# Sheet5.net
KiCad netlist of a schematic drawn in Altium Designer
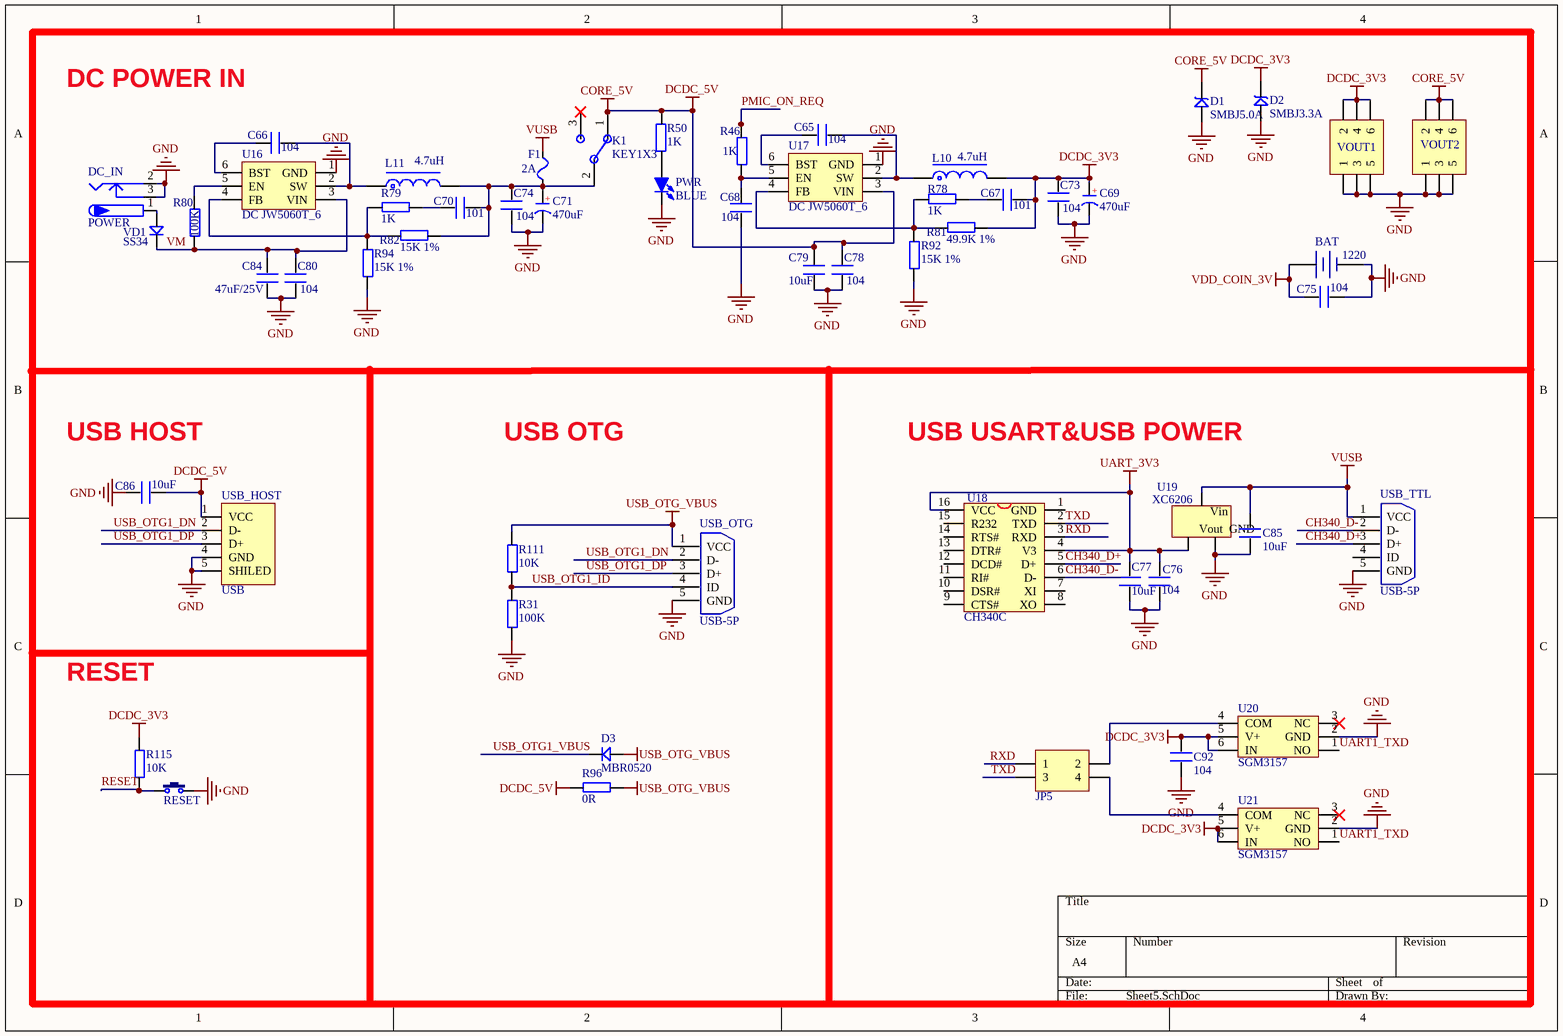
[diagram p0: Sheet5.SchDoc]

(export (version "E")
  (design (tool "Eeschema 10.0.6"))
  (components
    (comp (ref "BAT")
      (value "1220")
      (footprint "CR1220_B")
      (description "微型电池")
      (fields (field (name "版权归属") "源创客"))
      (libsource (lib "linux_board_SCH") (part "CR-3V"))
    )
    (comp (ref "C65") (value "104") (footprint "C 0603") (libsource (lib "linux_board_SCH") (part "C")))
    (comp (ref "C66") (value "104") (footprint "C 0603") (libsource (lib "linux_board_SCH") (part "C")))
    (comp (ref "C67") (value "101") (footprint "C 0603") (libsource (lib "linux_board_SCH") (part "C")))
    (comp (ref "C68") (value "104") (footprint "C 0603") (libsource (lib "linux_board_SCH") (part "C")))
    (comp (ref "C69")
      (value "470uF")
      (footprint "CM D(6.3*5.4)")
      (description "贴片电解电容")
      (fields (field (name "版权归属") "源创客"))
      (libsource (lib "linux_board_SCH") (part "C-CM"))
    )
    (comp (ref "C70") (value "101") (footprint "C 0603") (libsource (lib "linux_board_SCH") (part "C")))
    (comp (ref "C71")
      (value "470uF")
      (footprint "CM D(6.3*5.4)")
      (description "贴片电解电容")
      (fields (field (name "版权归属") "源创客"))
      (libsource (lib "linux_board_SCH") (part "C-CM"))
    )
    (comp (ref "C73") (value "104") (footprint "C 0603") (libsource (lib "linux_board_SCH") (part "C")))
    (comp (ref "C74") (value "104") (footprint "C 0603") (libsource (lib "linux_board_SCH") (part "C")))
    (comp (ref "C75") (value "104") (footprint "C 0603") (libsource (lib "linux_board_SCH") (part "C")))
    (comp (ref "C76") (value "104") (footprint "C 0603") (libsource (lib "linux_board_SCH") (part "C")))
    (comp (ref "C77") (value "10uF") (footprint "C 0603") (libsource (lib "linux_board_SCH") (part "C")))
    (comp (ref "C78") (value "104") (footprint "C 0603") (libsource (lib "linux_board_SCH") (part "C")))
    (comp (ref "C79") (value "10uF") (footprint "C 0603") (libsource (lib "linux_board_SCH") (part "C")))
    (comp (ref "C80") (value "104") (footprint "C 0603") (libsource (lib "linux_board_SCH") (part "C")))
    (comp (ref "C84") (value "47uF/25V") (footprint "C 0603") (libsource (lib "linux_board_SCH") (part "C")))
    (comp (ref "C85") (value "10uF") (footprint "C 0603") (libsource (lib "linux_board_SCH") (part "C")))
    (comp (ref "C86") (value "10uF") (footprint "C 0603") (libsource (lib "linux_board_SCH") (part "C")))
    (comp (ref "C92") (value "104") (footprint "C 0603") (libsource (lib "linux_board_SCH") (part "C")))
    (comp (ref "D1")
      (value "SMBJ5.0A")
      (footprint "SMBJ")
      (description "TVS")
      (libsource (lib "linux_board_SCH") (part "SMBJ"))
    )
    (comp (ref "D2")
      (value "SMBJ3.3A")
      (footprint "SMBJ")
      (description "TVS")
      (libsource (lib "linux_board_SCH") (part "SMBJ"))
    )
    (comp (ref "D3")
      (value "MBR0520")
      (footprint "SOD-123F")
      (description "肖特基二极管")
      (fields (field (name "版权归属") "源创客"))
      (libsource (lib "linux_board_SCH") (part "SS14"))
    )
    (comp (ref "DC_IN")
      (value "POWER")
      (footprint "DC10B")
      (description "低压电源接口")
      (fields (field (name "版权归属") "源创客"))
      (libsource (lib "linux_board_SCH") (part "P-DC"))
    )
    (comp (ref "F1")
      (value "2A")
      (footprint "FU 1206")
      (description "贴片保险丝")
      (fields (field (name "版权归属") "源创客"))
      (libsource (lib "linux_board_SCH") (part "FU"))
    )
    (comp (ref "JP5")
      (value "Header2X2")
      (footprint "HDR-2X2")
      (description "2*2P接插件")
      (fields (field (name "版权归属") "源创客"))
      (libsource (lib "linux_board_SCH") (part "Header 2X2"))
    )
    (comp (ref "K1") (value "KEY1X3") (footprint "PKEY") (libsource (lib "linux_board_SCH") (part "PKEY")))
    (comp (ref "L10")
      (value "4.7uH")
      (footprint "L-SMD-0420")
      (description "功率屏蔽电感")
      (fields (field (name "版权归属") "源创客"))
      (libsource (lib "linux_board_SCH") (part "L-CDRH"))
    )
    (comp (ref "L11")
      (value "4.7uH")
      (footprint "L-SMD-0420")
      (description "功率屏蔽电感")
      (fields (field (name "版权归属") "源创客"))
      (libsource (lib "linux_board_SCH") (part "L-CDRH"))
    )
    (comp (ref "PWR")
      (value "BLUE")
      (footprint "LED 0805R")
      (description "贴片LED")
      (fields (field (name "版权归属") "源创客"))
      (libsource (lib "linux_board_SCH") (part "LED-SMD"))
    )
    (comp (ref "R31") (value "100K") (footprint "R 0603") (libsource (lib "linux_board_SCH") (part "R")))
    (comp (ref "R46") (value "1K") (footprint "R 0603") (libsource (lib "linux_board_SCH") (part "R")))
    (comp (ref "R50") (value "1K") (footprint "R 0603") (libsource (lib "linux_board_SCH") (part "R")))
    (comp (ref "R78") (value "1K") (footprint "R 0603") (libsource (lib "linux_board_SCH") (part "R")))
    (comp (ref "R79") (value "1K") (footprint "R 0603") (libsource (lib "linux_board_SCH") (part "R")))
    (comp (ref "R80") (value "100K") (footprint "R 0603") (libsource (lib "linux_board_SCH") (part "R")))
    (comp (ref "R81") (value "49.9K 1%") (footprint "R 0603") (libsource (lib "linux_board_SCH") (part "R")))
    (comp (ref "R82") (value "15K 1%") (footprint "R 0603") (libsource (lib "linux_board_SCH") (part "R")))
    (comp (ref "R92") (value "15K 1%") (footprint "R 0603") (libsource (lib "linux_board_SCH") (part "R")))
    (comp (ref "R94") (value "15K 1%") (footprint "R 0603") (libsource (lib "linux_board_SCH") (part "R")))
    (comp (ref "R96") (value "0R") (footprint "R 0603") (libsource (lib "linux_board_SCH") (part "R")))
    (comp (ref "R111") (value "10K") (footprint "R 0603") (libsource (lib "linux_board_SCH") (part "R")))
    (comp (ref "R115") (value "10K") (footprint "R 0603") (libsource (lib "linux_board_SCH") (part "R")))
    (comp (ref "RESET")
      (value "KEY")
      (footprint "TSW DIP-6*6*5 - 2")
      (description "按键")
      (fields (field (name "版权归属") "源创客"))
      (libsource (lib "linux_board_SCH") (part "KEY"))
    )
    (comp (ref "U16")
      (value "DC JW5060T_6")
      (footprint "SOT23-6N")
      (description "DC降压芯片")
      (libsource (lib "linux_board_SCH") (part "DC JW5060T_6"))
    )
    (comp (ref "U17")
      (value "DC JW5060T_6")
      (footprint "SOT23-6N")
      (description "DC降压芯片")
      (libsource (lib "linux_board_SCH") (part "DC JW5060T_6"))
    )
    (comp (ref "U18")
      (value "CH340C")
      (footprint "SOP16_N")
      (description "USB2UART")
      (libsource (lib "linux_board_SCH") (part "CH340G"))
    )
    (comp (ref "U19")
      (value "XC6206")
      (footprint "SOT23-3N")
      (description "LDO")
      (libsource (lib "linux_board_SCH") (part "LDO XC6206"))
    )
    (comp (ref "U20")
      (value "SGM3157")
      (footprint "SOT363-6L")
      (description "单路双掷模拟开关")
      (libsource (lib "linux_board_SCH") (part "SGM3157"))
    )
    (comp (ref "U21")
      (value "SGM3157")
      (footprint "SOT363-6L")
      (description "单路双掷模拟开关")
      (libsource (lib "linux_board_SCH") (part "SGM3157"))
    )
    (comp (ref "USB_HOST")
      (value "USB")
      (footprint "USB-A/S_E")
      (description "USB-A型母接口")
      (fields (field (name "版权归属") "源创客"))
      (libsource (lib "linux_board_SCH") (part "USB-A/S"))
    )
    (comp (ref "USB_OTG")
      (value "USB-5P")
      (footprint "USB-MINI-A")
      (description "微型USB母座")
      (fields (field (name "版权归属") "源创客"))
      (libsource (lib "linux_board_SCH") (part "USB-5P"))
    )
    (comp (ref "USB_TTL")
      (value "USB-5P")
      (footprint "USB-MINI-A")
      (description "微型USB母座")
      (fields (field (name "版权归属") "源创客"))
      (libsource (lib "linux_board_SCH") (part "USB-5P"))
    )
    (comp (ref "VD1")
      (value "SS34")
      (footprint "SOD-323")
      (description "肖特基二极管")
      (fields (field (name "版权归属") "源创客"))
      (libsource (lib "linux_board_SCH") (part "SS14"))
    )
    (comp (ref "VOUT1")
      (value "RS232/RS485")
      (footprint "HDR-3X2")
      (description "3*2P接插件")
      (fields (field (name "版权归属") "源创客"))
      (libsource (lib "linux_board_SCH") (part "Header 3X2"))
    )
    (comp (ref "VOUT2")
      (value "RS232/RS485")
      (footprint "HDR-3X2")
      (description "3*2P接插件")
      (fields (field (name "版权归属") "源创客"))
      (libsource (lib "linux_board_SCH") (part "Header 3X2"))
    )
  )
  (nets
    (net (code "1") (name "/CH340_D+") (class "Default")
      (node (ref "U18") (pin "5") (pinfunction "D+_5") (pintype "passive"))
      (node (ref "USB_TTL") (pin "3") (pinfunction "D+_3") (pintype "passive"))
    )
    (net (code "2") (name "/CH340_D-") (class "Default")
      (node (ref "U18") (pin "6") (pinfunction "D-_6") (pintype "passive"))
      (node (ref "USB_TTL") (pin "2") (pinfunction "D-_2") (pintype "passive"))
    )
    (net (code "3") (name "/PMIC_ON_REQ") (class "Default") (node (ref "R46") (pin "2") (pintype "passive")))
    (net (code "4") (name "/RESET") (class "Default")
      (node (ref "R115") (pin "1") (pintype "passive"))
      (node (ref "RESET") (pin "1") (pinfunction "1_1") (pintype "passive"))
    )
    (net (code "5") (name "/RXD") (class "Default")
      (node (ref "JP5") (pin "1") (pinfunction "1_1") (pintype "passive"))
      (node (ref "U18") (pin "3") (pinfunction "RXD_3") (pintype "passive"))
    )
    (net (code "6") (name "/TXD") (class "Default")
      (node (ref "JP5") (pin "3") (pinfunction "3_3") (pintype "passive"))
      (node (ref "U18") (pin "2") (pinfunction "TXD_2") (pintype "passive"))
    )
    (net (code "7") (name "/UART1_TXD") (class "Default")
      (node (ref "U20") (pin "1") (pinfunction "NO_1") (pintype "passive"))
      (node (ref "U21") (pin "1") (pinfunction "NO_1") (pintype "passive"))
    )
    (net (code "8") (name "/USB_OTG1_DN") (class "Default")
      (node (ref "USB_HOST") (pin "2") (pinfunction "D-_2") (pintype "passive"))
      (node (ref "USB_OTG") (pin "2") (pinfunction "D-_2") (pintype "passive"))
    )
    (net (code "9") (name "/USB_OTG1_DP") (class "Default")
      (node (ref "USB_HOST") (pin "3") (pinfunction "D+_3") (pintype "passive"))
      (node (ref "USB_OTG") (pin "3") (pinfunction "D+_3") (pintype "passive"))
    )
    (net (code "10") (name "/USB_OTG1_ID") (class "Default")
      (node (ref "R111") (pin "1") (pintype "passive"))
      (node (ref "R31") (pin "2") (pintype "passive"))
      (node (ref "USB_OTG") (pin "4") (pinfunction "ID_4") (pintype "passive"))
    )
    (net (code "11") (name "/USB_OTG1_VBUS") (class "Default")
      (node (ref "D3") (pin "2") (pinfunction "K_2") (pintype "passive"))
    )
    (net (code "12") (name "/VM") (class "Default")
      (node (ref "C80") (pin "2") (pintype "passive"))
      (node (ref "C84") (pin "2") (pintype "passive"))
      (node (ref "R80") (pin "1") (pintype "passive"))
      (node (ref "U16") (pin "3") (pinfunction "VIN_3") (pintype "passive"))
      (node (ref "VD1") (pin "2") (pinfunction "K_2") (pintype "passive"))
    )
    (net (code "13") (name "CORE_5V") (class "Default")
      (node (ref "C78") (pin "2") (pintype "passive"))
      (node (ref "C79") (pin "2") (pintype "passive"))
      (node (ref "C86") (pin "1") (pintype "passive"))
      (node (ref "D1") (pin "2") (pintype "passive"))
      (node (ref "K1") (pin "1") (pintype "passive"))
      (node (ref "R50") (pin "1") (pintype "passive"))
      (node (ref "R96") (pin "2") (pintype "passive"))
      (node (ref "U17") (pin "3") (pinfunction "VIN_3") (pintype "passive"))
      (node (ref "USB_HOST") (pin "1") (pinfunction "VCC_1") (pintype "passive"))
      (node (ref "VOUT2") (pin "2") (pinfunction "2_2") (pintype "passive"))
      (node (ref "VOUT2") (pin "4") (pinfunction "4_4") (pintype "passive"))
      (node (ref "VOUT2") (pin "6") (pinfunction "6_6") (pintype "passive"))
    )
    (net (code "14") (name "DCDC_3V3") (class "Default")
      (node (ref "C67") (pin "2") (pintype "passive"))
      (node (ref "C69") (pin "1") (pinfunction "A_1") (pintype "passive"))
      (node (ref "C73") (pin "2") (pintype "passive"))
      (node (ref "C92") (pin "2") (pintype "passive"))
      (node (ref "D2") (pin "2") (pintype "passive"))
      (node (ref "L10") (pin "2") (pinfunction "2_2") (pintype "passive"))
      (node (ref "R115") (pin "2") (pintype "passive"))
      (node (ref "R81") (pin "1") (pintype "passive"))
      (node (ref "U20") (pin "5") (pinfunction "V+_5") (pintype "passive"))
      (node (ref "U20") (pin "6") (pinfunction "IN_6") (pintype "passive"))
      (node (ref "U21") (pin "5") (pinfunction "V+_5") (pintype "passive"))
      (node (ref "U21") (pin "6") (pinfunction "IN_6") (pintype "passive"))
      (node (ref "VOUT1") (pin "2") (pinfunction "2_2") (pintype "passive"))
      (node (ref "VOUT1") (pin "4") (pinfunction "4_4") (pintype "passive"))
      (node (ref "VOUT1") (pin "6") (pinfunction "6_6") (pintype "passive"))
    )
    (net (code "15") (name "GND") (class "Default")
      (node (ref "BAT") (pin "2") (pinfunction "DC-_2") (pintype "passive"))
      (node (ref "C68") (pin "1") (pintype "passive"))
      (node (ref "C69") (pin "2") (pinfunction "K_2") (pintype "passive"))
      (node (ref "C71") (pin "2") (pinfunction "K_2") (pintype "passive"))
      (node (ref "C73") (pin "1") (pintype "passive"))
      (node (ref "C74") (pin "1") (pintype "passive"))
      (node (ref "C75") (pin "2") (pintype "passive"))
      (node (ref "C76") (pin "1") (pintype "passive"))
      (node (ref "C77") (pin "1") (pintype "passive"))
      (node (ref "C78") (pin "1") (pintype "passive"))
      (node (ref "C79") (pin "1") (pintype "passive"))
      (node (ref "C80") (pin "1") (pintype "passive"))
      (node (ref "C84") (pin "1") (pintype "passive"))
      (node (ref "C85") (pin "1") (pintype "passive"))
      (node (ref "C86") (pin "2") (pintype "passive"))
      (node (ref "C92") (pin "1") (pintype "passive"))
      (node (ref "D1") (pin "1") (pintype "passive"))
      (node (ref "D2") (pin "1") (pintype "passive"))
      (node (ref "DC_IN") (pin "2") (pintype "power_in"))
      (node (ref "DC_IN") (pin "3") (pintype "power_in"))
      (node (ref "PWR") (pin "2") (pinfunction "K_2") (pintype "passive"))
      (node (ref "R31") (pin "1") (pintype "passive"))
      (node (ref "R92") (pin "1") (pintype "passive"))
      (node (ref "R94") (pin "1") (pintype "passive"))
      (node (ref "RESET") (pin "2") (pinfunction "2_2") (pintype "passive"))
      (node (ref "U16") (pin "1") (pinfunction "GND_1") (pintype "passive"))
      (node (ref "U17") (pin "1") (pinfunction "GND_1") (pintype "passive"))
      (node (ref "U19") (pin "1") (pinfunction "GND_1") (pintype "passive"))
      (node (ref "U20") (pin "2") (pinfunction "GND_2") (pintype "passive"))
      (node (ref "U21") (pin "2") (pinfunction "GND_2") (pintype "passive"))
      (node (ref "USB_HOST") (pin "4") (pinfunction "GND_4") (pintype "passive"))
      (node (ref "USB_HOST") (pin "5") (pinfunction "SHILED_5") (pintype "passive"))
      (node (ref "USB_OTG") (pin "5") (pinfunction "GND_5") (pintype "passive"))
      (node (ref "USB_TTL") (pin "5") (pinfunction "GND_5") (pintype "passive"))
      (node (ref "VOUT1") (pin "1") (pinfunction "1_1") (pintype "passive"))
      (node (ref "VOUT1") (pin "3") (pinfunction "3_3") (pintype "passive"))
      (node (ref "VOUT1") (pin "5") (pinfunction "5_5") (pintype "passive"))
      (node (ref "VOUT2") (pin "1") (pinfunction "1_1") (pintype "passive"))
      (node (ref "VOUT2") (pin "3") (pinfunction "3_3") (pintype "passive"))
      (node (ref "VOUT2") (pin "5") (pinfunction "5_5") (pintype "passive"))
    )
    (net (code "16") (name "Net-(C67-Pad1)") (class "Default")
      (node (ref "C67") (pin "1") (pintype "passive"))
      (node (ref "R78") (pin "1") (pintype "passive"))
    )
    (net (code "17") (name "Net-(C70-Pad1)") (class "Default")
      (node (ref "C70") (pin "1") (pintype "passive"))
      (node (ref "R79") (pin "1") (pintype "passive"))
    )
    (net (code "18") (name "Net-(C71-A)") (class "Default")
      (node (ref "C70") (pin "2") (pintype "passive"))
      (node (ref "C71") (pin "1") (pinfunction "A_1") (pintype "passive"))
      (node (ref "C74") (pin "2") (pintype "passive"))
      (node (ref "F1") (pin "1") (pinfunction "1_1") (pintype "passive"))
      (node (ref "K1") (pin "2") (pintype "passive"))
      (node (ref "L11") (pin "2") (pinfunction "2_2") (pintype "passive"))
      (node (ref "R82") (pin "1") (pintype "passive"))
    )
    (net (code "19") (name "Net-(PWR-A)") (class "Default")
      (node (ref "PWR") (pin "1") (pinfunction "A_1") (pintype "passive"))
      (node (ref "R50") (pin "2") (pintype "passive"))
    )
    (net (code "20") (name "Net-(U16-BST)") (class "Default")
      (node (ref "C66") (pin "1") (pintype "passive"))
      (node (ref "U16") (pin "6") (pinfunction "BST_6") (pintype "passive"))
    )
    (net (code "21") (name "Net-(U16-EN)") (class "Default")
      (node (ref "R80") (pin "2") (pintype "passive"))
      (node (ref "U16") (pin "5") (pinfunction "EN_5") (pintype "passive"))
    )
    (net (code "22") (name "Net-(U16-FB)") (class "Default")
      (node (ref "R79") (pin "2") (pintype "passive"))
      (node (ref "R82") (pin "2") (pintype "passive"))
      (node (ref "R94") (pin "2") (pintype "passive"))
      (node (ref "U16") (pin "4") (pinfunction "FB_4") (pintype "passive"))
    )
    (net (code "23") (name "Net-(U16-SW)") (class "Default")
      (node (ref "C66") (pin "2") (pintype "passive"))
      (node (ref "L11") (pin "1") (pinfunction "1_1") (pintype "passive"))
      (node (ref "U16") (pin "2") (pinfunction "SW_2") (pintype "passive"))
    )
    (net (code "24") (name "Net-(U17-BST)") (class "Default")
      (node (ref "C65") (pin "1") (pintype "passive"))
      (node (ref "U17") (pin "6") (pinfunction "BST_6") (pintype "passive"))
    )
    (net (code "25") (name "Net-(U17-EN)") (class "Default")
      (node (ref "C68") (pin "2") (pintype "passive"))
      (node (ref "R46") (pin "1") (pintype "passive"))
      (node (ref "U17") (pin "5") (pinfunction "EN_5") (pintype "passive"))
    )
    (net (code "26") (name "Net-(U17-FB)") (class "Default")
      (node (ref "R78") (pin "2") (pintype "passive"))
      (node (ref "R81") (pin "2") (pintype "passive"))
      (node (ref "R92") (pin "2") (pintype "passive"))
      (node (ref "U17") (pin "4") (pinfunction "FB_4") (pintype "passive"))
    )
    (net (code "27") (name "Net-(U17-SW)") (class "Default")
      (node (ref "C65") (pin "2") (pintype "passive"))
      (node (ref "L10") (pin "1") (pinfunction "1_1") (pintype "passive"))
      (node (ref "U17") (pin "2") (pinfunction "SW_2") (pintype "passive"))
    )
    (net (code "28") (name "Net-(U20-COM)") (class "Default")
      (node (ref "JP5") (pin "2") (pinfunction "2_2") (pintype "passive"))
      (node (ref "U20") (pin "4") (pinfunction "COM_4") (pintype "passive"))
    )
    (net (code "29") (name "Net-(U21-COM)") (class "Default")
      (node (ref "JP5") (pin "4") (pinfunction "4_4") (pintype "passive"))
      (node (ref "U21") (pin "4") (pinfunction "COM_4") (pintype "passive"))
    )
    (net (code "30") (name "Net-(VD1-A)") (class "Default")
      (node (ref "DC_IN") (pin "1") (pintype "power_in"))
      (node (ref "VD1") (pin "1") (pinfunction "A_1") (pintype "passive"))
    )
    (net (code "31") (name "UART_3V3") (class "Default")
      (node (ref "C76") (pin "2") (pintype "passive"))
      (node (ref "C77") (pin "2") (pintype "passive"))
      (node (ref "U18") (pin "16") (pinfunction "VCC_16") (pintype "passive"))
      (node (ref "U18") (pin "4") (pinfunction "V3_4") (pintype "passive"))
      (node (ref "U19") (pin "2") (pinfunction "Vout_2") (pintype "passive"))
    )
    (net (code "32") (name "USB_OTG_VBUS") (class "Default")
      (node (ref "D3") (pin "1") (pinfunction "A_1") (pintype "passive"))
      (node (ref "R111") (pin "2") (pintype "passive"))
      (node (ref "R96") (pin "1") (pintype "passive"))
      (node (ref "USB_OTG") (pin "1") (pinfunction "VCC_1") (pintype "passive"))
    )
    (net (code "33") (name "VDD_COIN_3V") (class "Default")
      (node (ref "BAT") (pin "1") (pinfunction "DC+_1") (pintype "passive"))
      (node (ref "C75") (pin "1") (pintype "passive"))
    )
    (net (code "34") (name "VUSB") (class "Default")
      (node (ref "C85") (pin "2") (pintype "passive"))
      (node (ref "F1") (pin "2") (pinfunction "2_2") (pintype "passive"))
      (node (ref "U19") (pin "3") (pinfunction "Vin_3") (pintype "passive"))
      (node (ref "USB_TTL") (pin "1") (pinfunction "VCC_1") (pintype "passive"))
    )
    (net (code "35") (name "unconnected-(K1-Pad3)") (class "Default")
      (node (ref "K1") (pin "3") (pintype "passive+no_connect"))
    )
    (net (code "36") (name "unconnected-(U18-CTS#-Pad9)") (class "Default")
      (node (ref "U18") (pin "9") (pinfunction "CTS#_9") (pintype "passive"))
    )
    (net (code "37") (name "unconnected-(U18-DCD#-Pad12)") (class "Default")
      (node (ref "U18") (pin "12") (pinfunction "DCD#_12") (pintype "passive"))
    )
    (net (code "38") (name "unconnected-(U18-DSR#-Pad10)") (class "Default")
      (node (ref "U18") (pin "10") (pinfunction "DSR#_10") (pintype "passive"))
    )
    (net (code "39") (name "unconnected-(U18-DTR#-Pad13)") (class "Default")
      (node (ref "U18") (pin "13") (pinfunction "DTR#_13") (pintype "passive"))
    )
    (net (code "40") (name "unconnected-(U18-GND-Pad1)") (class "Default")
      (node (ref "U18") (pin "1") (pinfunction "GND_1") (pintype "passive"))
    )
    (net (code "41") (name "unconnected-(U18-R232-Pad15)") (class "Default")
      (node (ref "U18") (pin "15") (pinfunction "R232_15") (pintype "passive"))
    )
    (net (code "42") (name "unconnected-(U18-RI#-Pad11)") (class "Default")
      (node (ref "U18") (pin "11") (pinfunction "RI#_11") (pintype "passive"))
    )
    (net (code "43") (name "unconnected-(U18-RTS#-Pad14)") (class "Default")
      (node (ref "U18") (pin "14") (pinfunction "RTS#_14") (pintype "passive"))
    )
    (net (code "44") (name "unconnected-(U18-XI-Pad7)") (class "Default")
      (node (ref "U18") (pin "7") (pinfunction "XI_7") (pintype "passive"))
    )
    (net (code "45") (name "unconnected-(U18-XO-Pad8)") (class "Default")
      (node (ref "U18") (pin "8") (pinfunction "XO_8") (pintype "passive"))
    )
    (net (code "46") (name "unconnected-(U20-NC-Pad3)") (class "Default")
      (node (ref "U20") (pin "3") (pinfunction "NC_3") (pintype "passive+no_connect"))
    )
    (net (code "47") (name "unconnected-(U21-NC-Pad3)") (class "Default")
      (node (ref "U21") (pin "3") (pinfunction "NC_3") (pintype "passive+no_connect"))
    )
    (net (code "48") (name "unconnected-(USB_TTL-ID-Pad4)") (class "Default")
      (node (ref "USB_TTL") (pin "4") (pinfunction "ID_4") (pintype "passive"))
    )
  )
)
